# Connectors.net
KiCad netlist of a schematic drawn in Altium Designer
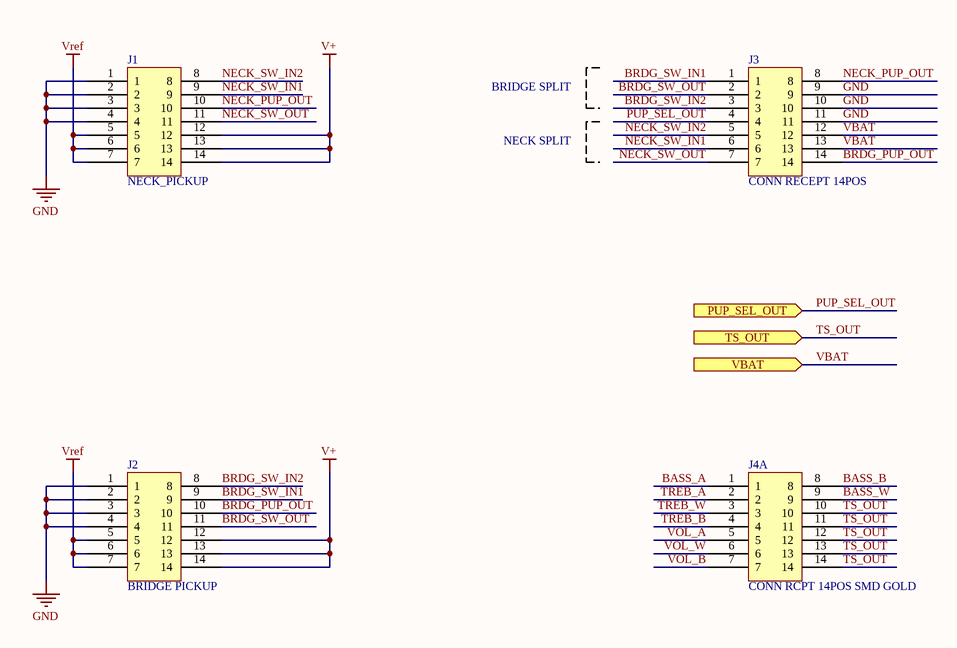
[diagram p0: Connectors.SchDoc]

(export (version "E")
  (design (tool "Eeschema 10.0.6"))
  (components
    (comp (ref "J1")
      (value "CONN HEADER 14POS")
      (footprint "DF12(3.0)-14DP")
      (description "14 Position Connector Header, Outer Shroud Contacts Surface Mount Gold")
      (fields (field (name "MANUFACTURER") "Hirose") (field (name "DIGIKEY PART NUMBER") "H11701CT-ND"))
      (libsource (lib "GuitarLibrary") (part "DF12(3.0)-14DP-0.5V(86)"))
    )
    (comp (ref "J2")
      (value "CONN HEADER 14POS")
      (footprint "DF12(3.0)-14DP")
      (description "14 Position Connector Header, Outer Shroud Contacts Surface Mount Gold")
      (fields (field (name "MANUFACTURER") "Hirose") (field (name "DIGIKEY PART NUMBER") "H11701CT-ND"))
      (libsource (lib "GuitarLibrary") (part "DF12(3.0)-14DP-0.5V(86)"))
    )
    (comp (ref "J3")
      (value "CONN RECEPT 14POS")
      (footprint "DF12(3.0)-14DS")
      (description "14 Position Connector Receptacle, Center Strip Contacts Surface Mount Gold")
      (fields (field (name "MANUFACTURER") "Hirose") (field (name "DIGIKEY PART NUMBER") "H11702CT-ND"))
      (libsource (lib "GuitarLibrary") (part "DF12(3.0)-14DS-0.5V(86)"))
    )
    (comp (ref "J4")
      (value "CONN RCPT 14POS SMD GOLD")
      (footprint "DF12(3.0)-14DS")
      (description "14 Position Connector Header, Outer Shroud Contacts Surface Mount Gold")
      (fields (field (name "MANUFACTURER") "Hirose") (field (name "DIGIKEY PART NUMBER") "H11702CT-ND"))
      (libsource (lib "GuitarLibrary") (part "DF12(3.0)-14DS-0.5V(86)-COMPOSITE"))
    )
  )
  (nets
    (net (code "1") (name "/BASS_A") (class "Default")
      (node (ref "J4") (pin "1") (pinfunction "1_1") (pintype "passive"))
    )
    (net (code "2") (name "/BASS_B") (class "Default")
      (node (ref "J4") (pin "8") (pinfunction "8_8") (pintype "passive"))
    )
    (net (code "3") (name "/BASS_W") (class "Default")
      (node (ref "J4") (pin "9") (pinfunction "9_9") (pintype "passive"))
    )
    (net (code "4") (name "/BRDG_PUP_OUT") (class "Default")
      (node (ref "J2") (pin "10") (pinfunction "10_10") (pintype "passive"))
      (node (ref "J3") (pin "14") (pinfunction "14_14") (pintype "passive"))
    )
    (net (code "5") (name "/BRDG_SW_IN1") (class "Default")
      (node (ref "J2") (pin "9") (pinfunction "9_9") (pintype "passive"))
      (node (ref "J3") (pin "1") (pinfunction "1_1") (pintype "passive"))
    )
    (net (code "6") (name "/BRDG_SW_IN2") (class "Default")
      (node (ref "J2") (pin "8") (pinfunction "8_8") (pintype "passive"))
      (node (ref "J3") (pin "3") (pinfunction "3_3") (pintype "passive"))
    )
    (net (code "7") (name "/BRDG_SW_OUT") (class "Default")
      (node (ref "J2") (pin "11") (pinfunction "11_11") (pintype "passive"))
      (node (ref "J3") (pin "2") (pinfunction "2_2") (pintype "passive"))
    )
    (net (code "8") (name "/NECK_PUP_OUT") (class "Default")
      (node (ref "J1") (pin "10") (pinfunction "10_10") (pintype "passive"))
      (node (ref "J3") (pin "8") (pinfunction "8_8") (pintype "passive"))
    )
    (net (code "9") (name "/NECK_SW_IN1") (class "Default")
      (node (ref "J1") (pin "9") (pinfunction "9_9") (pintype "passive"))
      (node (ref "J3") (pin "6") (pinfunction "6_6") (pintype "passive"))
    )
    (net (code "10") (name "/NECK_SW_IN2") (class "Default")
      (node (ref "J1") (pin "8") (pinfunction "8_8") (pintype "passive"))
      (node (ref "J3") (pin "5") (pinfunction "5_5") (pintype "passive"))
    )
    (net (code "11") (name "/NECK_SW_OUT") (class "Default")
      (node (ref "J1") (pin "11") (pinfunction "11_11") (pintype "passive"))
      (node (ref "J3") (pin "7") (pinfunction "7_7") (pintype "passive"))
    )
    (net (code "12") (name "/PUP_SEL_OUT") (class "Default")
      (node (ref "J3") (pin "4") (pinfunction "4_4") (pintype "passive"))
    )
    (net (code "13") (name "/TREB_A") (class "Default")
      (node (ref "J4") (pin "2") (pinfunction "2_2") (pintype "passive"))
    )
    (net (code "14") (name "/TREB_B") (class "Default")
      (node (ref "J4") (pin "4") (pinfunction "4_4") (pintype "passive"))
    )
    (net (code "15") (name "/TREB_W") (class "Default")
      (node (ref "J4") (pin "3") (pinfunction "3_3") (pintype "passive"))
    )
    (net (code "16") (name "/TS_OUT") (class "Default")
      (node (ref "J4") (pin "10") (pinfunction "10_10") (pintype "passive"))
      (node (ref "J4") (pin "11") (pinfunction "11_11") (pintype "passive"))
      (node (ref "J4") (pin "12") (pinfunction "12_12") (pintype "passive"))
      (node (ref "J4") (pin "13") (pinfunction "13_13") (pintype "passive"))
      (node (ref "J4") (pin "14") (pinfunction "14_14") (pintype "passive"))
    )
    (net (code "17") (name "/VBAT") (class "Default")
      (node (ref "J3") (pin "12") (pinfunction "12_12") (pintype "passive"))
      (node (ref "J3") (pin "13") (pinfunction "13_13") (pintype "passive"))
    )
    (net (code "18") (name "/VOL_A") (class "Default")
      (node (ref "J4") (pin "5") (pinfunction "5_5") (pintype "passive"))
    )
    (net (code "19") (name "/VOL_B") (class "Default")
      (node (ref "J4") (pin "7") (pinfunction "7_7") (pintype "passive"))
    )
    (net (code "20") (name "/VOL_W") (class "Default")
      (node (ref "J4") (pin "6") (pinfunction "6_6") (pintype "passive"))
    )
    (net (code "21") (name "GND") (class "Default")
      (node (ref "J1") (pin "1") (pinfunction "1_1") (pintype "passive"))
      (node (ref "J1") (pin "2") (pinfunction "2_2") (pintype "passive"))
      (node (ref "J1") (pin "3") (pinfunction "3_3") (pintype "passive"))
      (node (ref "J1") (pin "4") (pinfunction "4_4") (pintype "passive"))
      (node (ref "J2") (pin "1") (pinfunction "1_1") (pintype "passive"))
      (node (ref "J2") (pin "2") (pinfunction "2_2") (pintype "passive"))
      (node (ref "J2") (pin "3") (pinfunction "3_3") (pintype "passive"))
      (node (ref "J2") (pin "4") (pinfunction "4_4") (pintype "passive"))
      (node (ref "J3") (pin "10") (pinfunction "10_10") (pintype "passive"))
      (node (ref "J3") (pin "11") (pinfunction "11_11") (pintype "passive"))
      (node (ref "J3") (pin "9") (pinfunction "9_9") (pintype "passive"))
    )
    (net (code "22") (name "V+") (class "Default")
      (node (ref "J1") (pin "12") (pinfunction "12_12") (pintype "passive"))
      (node (ref "J1") (pin "13") (pinfunction "13_13") (pintype "passive"))
      (node (ref "J1") (pin "14") (pinfunction "14_14") (pintype "passive"))
      (node (ref "J2") (pin "12") (pinfunction "12_12") (pintype "passive"))
      (node (ref "J2") (pin "13") (pinfunction "13_13") (pintype "passive"))
      (node (ref "J2") (pin "14") (pinfunction "14_14") (pintype "passive"))
    )
    (net (code "23") (name "Vref") (class "Default")
      (node (ref "J1") (pin "5") (pinfunction "5_5") (pintype "passive"))
      (node (ref "J1") (pin "6") (pinfunction "6_6") (pintype "passive"))
      (node (ref "J1") (pin "7") (pinfunction "7_7") (pintype "passive"))
      (node (ref "J2") (pin "5") (pinfunction "5_5") (pintype "passive"))
      (node (ref "J2") (pin "6") (pinfunction "6_6") (pintype "passive"))
      (node (ref "J2") (pin "7") (pinfunction "7_7") (pintype "passive"))
    )
  )
)
